# Sensing_ADC_Buffering.net
KiCad netlist of a schematic drawn in Altium Designer
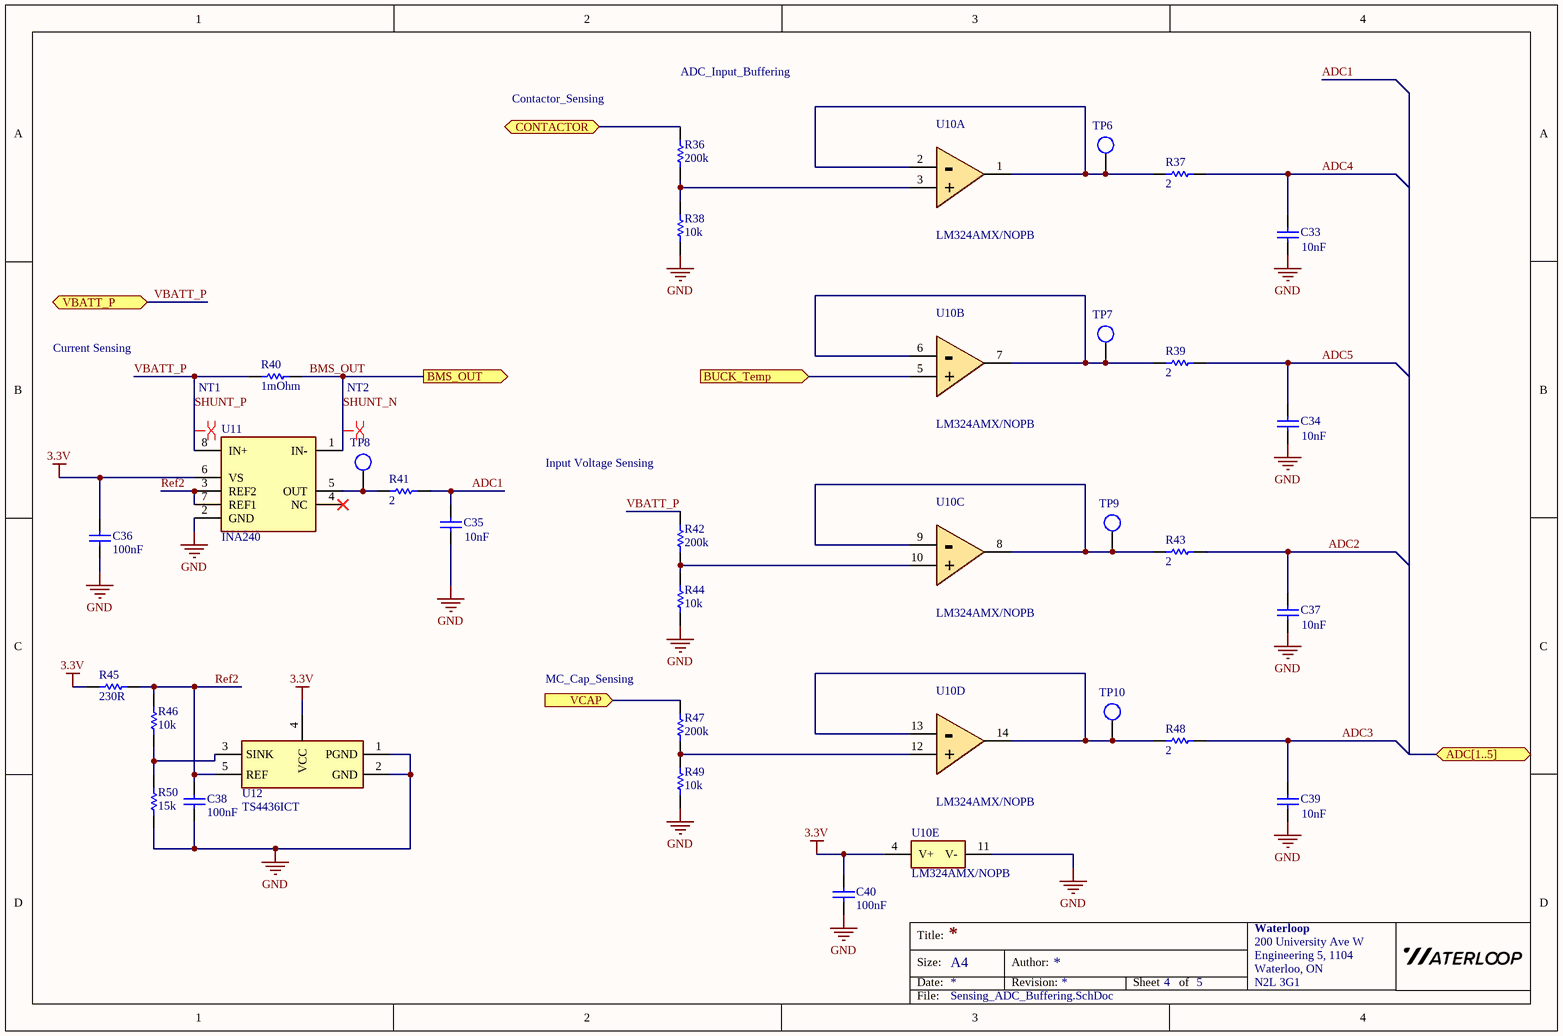
[diagram p0: Sensing_ADC_Buffering.SchDoc]

(export (version "E")
  (design (tool "Eeschema 10.0.6"))
  (components
    (comp (ref "C33")
      (value "10nF")
      (footprint "0805 - Capacitor")
      (description "CC0805JRX7R9BB103, CAP CER 10000PF 50V X7R 0805")
      (fields
        (field (name "MANUFACTURER") "YAGEO")
        (field (name "MANUFACTURER PART NUMBER") "CC0805MRX7R9BB103")
      )
      (libsource (lib "General") (part "Capacitor - Nonpolarized"))
    )
    (comp (ref "C34")
      (value "10nF")
      (footprint "0805 - Capacitor")
      (description "CC0805JRX7R9BB103, CAP CER 10000PF 50V X7R 0805")
      (fields
        (field (name "MANUFACTURER") "YAGEO")
        (field (name "MANUFACTURER PART NUMBER") "CC0805MRX7R9BB103")
      )
      (libsource (lib "General") (part "Capacitor - Nonpolarized"))
    )
    (comp (ref "C35")
      (value "10nF")
      (footprint "0805 - Capacitor")
      (description "CC0805JRX7R9BB103, CAP CER 10000PF 50V X7R 0805")
      (fields
        (field (name "MANUFACTURER") "YAGEO")
        (field (name "MANUFACTURER PART NUMBER") "CC0805MRX7R9BB103")
      )
      (libsource (lib "General") (part "Capacitor - Nonpolarized"))
    )
    (comp (ref "C36")
      (value "100nF")
      (footprint "0805 - Capacitor")
      (description "CC0805KRX7R9BB104, 0.1 µF  \r\n±10% 50V Ceramic Capacitor X7R 0805 (2012 Metric)")
      (fields
        (field (name "MANUFACTURER") "YAGEO")
        (field (name "MANUFACTURER PART NUMBER") "CC0805KRX7R9BB104")
      )
      (libsource (lib "General") (part "Capacitor - Nonpolarized"))
    )
    (comp (ref "C37")
      (value "10nF")
      (footprint "0805 - Capacitor")
      (description "CC0805JRX7R9BB103, CAP CER 10000PF 50V X7R 0805")
      (fields
        (field (name "MANUFACTURER") "YAGEO")
        (field (name "MANUFACTURER PART NUMBER") "CC0805MRX7R9BB103")
      )
      (libsource (lib "General") (part "Capacitor - Nonpolarized"))
    )
    (comp (ref "C38")
      (value "100nF")
      (footprint "0805 - Capacitor")
      (description "CC0805KRX7R9BB104, 0.1 µF  \r\n±10% 50V Ceramic Capacitor X7R 0805 (2012 Metric)")
      (fields
        (field (name "MANUFACTURER") "YAGEO")
        (field (name "MANUFACTURER PART NUMBER") "CC0805KRX7R9BB104")
      )
      (libsource (lib "General") (part "Capacitor - Nonpolarized"))
    )
    (comp (ref "C39")
      (value "10nF")
      (footprint "0805 - Capacitor")
      (description "CC0805JRX7R9BB103, CAP CER 10000PF 50V X7R 0805")
      (fields
        (field (name "MANUFACTURER") "YAGEO")
        (field (name "MANUFACTURER PART NUMBER") "CC0805MRX7R9BB103")
      )
      (libsource (lib "General") (part "Capacitor - Nonpolarized"))
    )
    (comp (ref "C40")
      (value "100nF")
      (footprint "0805 - Capacitor")
      (description "CC0805KRX7R9BB104, 0.1 µF  \r\n±10% 50V Ceramic Capacitor X7R 0805 (2012 Metric)")
      (fields
        (field (name "MANUFACTURER") "YAGEO")
        (field (name "MANUFACTURER PART NUMBER") "CC0805KRX7R9BB104")
      )
      (libsource (lib "General") (part "Capacitor - Nonpolarized"))
    )
    (comp (ref "NT1") (value "NetTie") (footprint "Net Tie") (libsource (lib "General") (part "Net Tie")))
    (comp (ref "NT2") (value "NetTie") (footprint "Net Tie") (libsource (lib "General") (part "Net Tie")))
    (comp (ref "R36")
      (value "200k")
      (footprint "0603 - Resistor")
      (description "RC0603FR-07200KL. 200 kOhms ±1% 0.1W, 1/10W Chip Resistor 0603 (1608 Metric) Thick Film")
      (fields
        (field (name "MANUFACTURER PART NUMBER") "RC0603FR-07200KL")
        (field (name "MANUFACTURER") "YAGEO")
      )
      (libsource (lib "General") (part "Resistor"))
    )
    (comp (ref "R37")
      (value "2")
      (footprint "0603 - Resistor")
      (description "RC0603FR-072RL, RES 2 OHM 1% 1/10W 0603")
      (fields
        (field (name "MANUFACTURER PART NUMBER") "RC0603FR-072RL")
        (field (name "MANUFACTURER") "YAGEO")
      )
      (libsource (lib "General") (part "Resistor"))
    )
    (comp (ref "R38")
      (value "10k")
      (footprint "0603 - Resistor")
      (fields
        (field (name "MANUFACTURER PART NUMBER") "RC0603FR-0710KL")
        (field (name "MANUFACTURER") "Yageo")
        (field (name "Comment") "Res2")
      )
      (libsource (lib "General") (part "Resistor"))
    )
    (comp (ref "R39")
      (value "2")
      (footprint "0603 - Resistor")
      (description "RC0603FR-072RL, RES 2 OHM 1% 1/10W 0603")
      (fields
        (field (name "MANUFACTURER PART NUMBER") "RC0603FR-072RL")
        (field (name "MANUFACTURER") "YAGEO")
      )
      (libsource (lib "General") (part "Resistor"))
    )
    (comp (ref "R40")
      (value "1mOhm")
      (footprint "2512 - RESISTOR")
      (description "SCMM2512S5-R001F, RES 0.001 OHM 1% 5W 2512")
      (fields
        (field (name "MANUFACTURER PART NUMBER") "VSML2512S5-R001F")
        (field (name "MANUFACTURER") "Delta Electronics/Cyntec")
      )
      (libsource (lib "General") (part "Resistor"))
    )
    (comp (ref "R41")
      (value "2")
      (footprint "0603 - Resistor")
      (description "RC0603FR-072RL, RES 2 OHM 1% 1/10W 0603")
      (fields
        (field (name "MANUFACTURER PART NUMBER") "RC0603FR-072RL")
        (field (name "MANUFACTURER") "YAGEO")
      )
      (libsource (lib "General") (part "Resistor"))
    )
    (comp (ref "R42")
      (value "200k")
      (footprint "0603 - Resistor")
      (description "RC0603FR-07200KL. 200 kOhms ±1% 0.1W, 1/10W Chip Resistor 0603 (1608 Metric) Thick Film")
      (fields
        (field (name "MANUFACTURER PART NUMBER") "RC0603FR-07200KL")
        (field (name "MANUFACTURER") "YAGEO")
      )
      (libsource (lib "General") (part "Resistor"))
    )
    (comp (ref "R43")
      (value "2")
      (footprint "0603 - Resistor")
      (description "RC0603FR-072RL, RES 2 OHM 1% 1/10W 0603")
      (fields
        (field (name "MANUFACTURER PART NUMBER") "RC0603FR-072RL")
        (field (name "MANUFACTURER") "YAGEO")
      )
      (libsource (lib "General") (part "Resistor"))
    )
    (comp (ref "R44")
      (value "10k")
      (footprint "0603 - Resistor")
      (fields
        (field (name "MANUFACTURER PART NUMBER") "RC0603FR-0710KL")
        (field (name "MANUFACTURER") "Yageo")
        (field (name "Comment") "Res2")
      )
      (libsource (lib "General") (part "Resistor"))
    )
    (comp (ref "R45")
      (value "230R")
      (footprint "0603 - Resistor")
      (fields
        (field (name "MANUFACTURER PART NUMBER") "RC0603FR-07232RL")
        (field (name "MANUFACTURER") "YAGEO")
        (field (name "Comment") "Res2")
      )
      (libsource (lib "General") (part "Resistor"))
    )
    (comp (ref "R46")
      (value "10k")
      (footprint "0603 - Resistor")
      (fields
        (field (name "MANUFACTURER PART NUMBER") "RC0603FR-0710KL")
        (field (name "MANUFACTURER") "Yageo")
        (field (name "Comment") "Res2")
      )
      (libsource (lib "General") (part "Resistor"))
    )
    (comp (ref "R47")
      (value "200k")
      (footprint "0603 - Resistor")
      (description "RC0603FR-07200KL. 200 kOhms ±1% 0.1W, 1/10W Chip Resistor 0603 (1608 Metric) Thick Film")
      (fields
        (field (name "MANUFACTURER PART NUMBER") "RC0603FR-07200KL")
        (field (name "MANUFACTURER") "YAGEO")
      )
      (libsource (lib "General") (part "Resistor"))
    )
    (comp (ref "R48")
      (value "2")
      (footprint "0603 - Resistor")
      (description "RC0603FR-072RL, RES 2 OHM 1% 1/10W 0603")
      (fields
        (field (name "MANUFACTURER PART NUMBER") "RC0603FR-072RL")
        (field (name "MANUFACTURER") "YAGEO")
      )
      (libsource (lib "General") (part "Resistor"))
    )
    (comp (ref "R49")
      (value "10k")
      (footprint "0603 - Resistor")
      (fields
        (field (name "MANUFACTURER PART NUMBER") "ERJ-3GEYJ103V")
        (field (name "MANUFACTURER") "Panasonic Electronic Components")
      )
      (libsource (lib "General") (part "Resistor"))
    )
    (comp (ref "R50")
      (value "15k")
      (footprint "0603 - Resistor")
      (fields
        (field (name "MANUFACTURER PART NUMBER") "RC0603FR-0715KL")
        (field (name "MANUFACTURER") "YAGEO")
        (field (name "Comment") "Res2")
      )
      (libsource (lib "General") (part "Resistor"))
    )
    (comp (ref "TP6")
      (value "~")
      (footprint "Test Point - 5002")
      (description "Test Point")
      (libsource (lib "General") (part "Test Point"))
    )
    (comp (ref "TP7")
      (value "~")
      (footprint "Test Point - 5002")
      (description "Test Point")
      (libsource (lib "General") (part "Test Point"))
    )
    (comp (ref "TP8")
      (value "~")
      (footprint "Test Point - 5002")
      (description "Test Point")
      (libsource (lib "General") (part "Test Point"))
    )
    (comp (ref "TP9")
      (value "~")
      (footprint "Test Point - 5002")
      (description "Test Point")
      (libsource (lib "General") (part "Test Point"))
    )
    (comp (ref "TP10")
      (value "~")
      (footprint "Test Point - 5002")
      (description "Test Point")
      (libsource (lib "General") (part "Test Point"))
    )
    (comp (ref "U10")
      (value "LM324AMX/NOPB")
      (footprint "LM324AMX/NOPB")
      (description "LM324AMX/NOPB, Gen Purp 4Ch Opamp")
      (fields (field (name "MANUFACTURER") "TI"))
      (libsource (lib "GeneralComponents") (part "LM324AMX/NOPB"))
    )
    (comp (ref "U11")
      (value "INA240")
      (footprint "INA240")
      (description "INA240A2, -4V to 80V Current Sense Amplifier")
      (fields
        (field (name "MANUFACTURER") "Texas Instruments")
        (field (name "MANUFACTURER PART NUMBER") "INA240A2DR")
      )
      (libsource (lib "GeneralComponents") (part "INA240"))
    )
    (comp (ref "U12")
      (value "TS4436ICT")
      (footprint "SOT323")
      (description "Shunt Voltage Reference IC Adjustable 0.6V 1.8 VV ±1% 20 mA SC-70-5")
      (fields (field (name "MANUFACTURER") "ST"))
      (libsource (lib "GeneralComponents") (part "TS4436ICT"))
    )
  )
  (nets
    (net (code "1") (name "/ADC1") (class "Default")
      (node (ref "C35") (pin "2") (pinfunction "2_2") (pintype "passive"))
      (node (ref "R41") (pin "2") (pinfunction "2_2") (pintype "passive"))
    )
    (net (code "2") (name "/ADC2") (class "Default")
      (node (ref "C37") (pin "2") (pinfunction "2_2") (pintype "passive"))
      (node (ref "R43") (pin "2") (pinfunction "2_2") (pintype "passive"))
    )
    (net (code "3") (name "/ADC3") (class "Default")
      (node (ref "C39") (pin "2") (pinfunction "2_2") (pintype "passive"))
      (node (ref "R48") (pin "2") (pinfunction "2_2") (pintype "passive"))
    )
    (net (code "4") (name "/ADC4") (class "Default")
      (node (ref "C33") (pin "2") (pinfunction "2_2") (pintype "passive"))
      (node (ref "R37") (pin "2") (pinfunction "2_2") (pintype "passive"))
    )
    (net (code "5") (name "/ADC5") (class "Default")
      (node (ref "C34") (pin "2") (pinfunction "2_2") (pintype "passive"))
      (node (ref "R39") (pin "2") (pinfunction "2_2") (pintype "passive"))
    )
    (net (code "7") (name "/BMS_OUT") (class "Default")
      (node (ref "NT2") (pin "2") (pinfunction "2_2") (pintype "passive"))
      (node (ref "R40") (pin "2") (pinfunction "2_2") (pintype "passive"))
    )
    (net (code "8") (name "/BUCK_Temp") (class "Default")
      (node (ref "U10") (pin "5") (pinfunction "+_5") (pintype "passive"))
    )
    (net (code "9") (name "/CONTACTOR") (class "Default")
      (node (ref "R36") (pin "2") (pinfunction "2_2") (pintype "passive"))
    )
    (net (code "10") (name "/Ref2") (class "Default")
      (node (ref "C38") (pin "2") (pinfunction "2_2") (pintype "passive"))
      (node (ref "R45") (pin "1") (pinfunction "1_1") (pintype "passive"))
      (node (ref "R46") (pin "1") (pinfunction "1_1") (pintype "passive"))
      (node (ref "U11") (pin "3") (pinfunction "REF2_3") (pintype "passive"))
      (node (ref "U11") (pin "7") (pinfunction "REF1_7") (pintype "passive"))
      (node (ref "U12") (pin "5") (pinfunction "REF_5") (pintype "passive"))
    )
    (net (code "11") (name "/SHUNT_N") (class "Default")
      (node (ref "NT2") (pin "1") (pinfunction "1_1") (pintype "passive"))
      (node (ref "U11") (pin "1") (pinfunction "IN-_1") (pintype "passive"))
    )
    (net (code "12") (name "/SHUNT_P") (class "Default")
      (node (ref "NT1") (pin "1") (pinfunction "1_1") (pintype "passive"))
      (node (ref "U11") (pin "8") (pinfunction "IN+_8") (pintype "passive"))
    )
    (net (code "13") (name "/VBATT_P") (class "Default")
      (node (ref "NT1") (pin "2") (pinfunction "2_2") (pintype "passive"))
      (node (ref "R40") (pin "1") (pinfunction "1_1") (pintype "passive"))
      (node (ref "R42") (pin "2") (pinfunction "2_2") (pintype "passive"))
    )
    (net (code "14") (name "/VCAP") (class "Default")
      (node (ref "R47") (pin "2") (pinfunction "2_2") (pintype "passive"))
    )
    (net (code "15") (name "3.3V") (class "Default")
      (node (ref "C36") (pin "2") (pinfunction "2_2") (pintype "passive"))
      (node (ref "C40") (pin "2") (pinfunction "2_2") (pintype "passive"))
      (node (ref "R45") (pin "2") (pinfunction "2_2") (pintype "passive"))
      (node (ref "U10") (pin "4") (pinfunction "V+_4") (pintype "passive"))
      (node (ref "U11") (pin "6") (pinfunction "VS_6") (pintype "power_in"))
      (node (ref "U12") (pin "4") (pinfunction "VCC_4") (pintype "passive"))
    )
    (net (code "16") (name "GND") (class "Default")
      (node (ref "C33") (pin "1") (pinfunction "1_1") (pintype "passive"))
      (node (ref "C34") (pin "1") (pinfunction "1_1") (pintype "passive"))
      (node (ref "C35") (pin "1") (pinfunction "1_1") (pintype "passive"))
      (node (ref "C36") (pin "1") (pinfunction "1_1") (pintype "passive"))
      (node (ref "C37") (pin "1") (pinfunction "1_1") (pintype "passive"))
      (node (ref "C38") (pin "1") (pinfunction "1_1") (pintype "passive"))
      (node (ref "C39") (pin "1") (pinfunction "1_1") (pintype "passive"))
      (node (ref "C40") (pin "1") (pinfunction "1_1") (pintype "passive"))
      (node (ref "R38") (pin "1") (pinfunction "1_1") (pintype "passive"))
      (node (ref "R44") (pin "1") (pinfunction "1_1") (pintype "passive"))
      (node (ref "R49") (pin "1") (pinfunction "1_1") (pintype "passive"))
      (node (ref "R50") (pin "2") (pinfunction "2_2") (pintype "passive"))
      (node (ref "U10") (pin "11") (pinfunction "V-_11") (pintype "passive"))
      (node (ref "U11") (pin "2") (pinfunction "GND_2") (pintype "power_in"))
      (node (ref "U12") (pin "1") (pinfunction "PGND_1") (pintype "passive"))
      (node (ref "U12") (pin "2") (pinfunction "GND_2") (pintype "passive"))
    )
    (net (code "17") (name "Net-(TP6-0)") (class "Default")
      (node (ref "R37") (pin "1") (pinfunction "1_1") (pintype "passive"))
      (node (ref "TP6") (pin "1") (pinfunction "0_1") (pintype "passive"))
      (node (ref "U10") (pin "1") (pinfunction "14_1") (pintype "passive"))
      (node (ref "U10") (pin "2") (pinfunction "-_2") (pintype "passive"))
    )
    (net (code "18") (name "Net-(TP7-0)") (class "Default")
      (node (ref "R39") (pin "1") (pinfunction "1_1") (pintype "passive"))
      (node (ref "TP7") (pin "1") (pinfunction "0_1") (pintype "passive"))
      (node (ref "U10") (pin "6") (pinfunction "-_6") (pintype "passive"))
      (node (ref "U10") (pin "7") (pinfunction "14_7") (pintype "passive"))
    )
    (net (code "19") (name "Net-(TP8-0)") (class "Default")
      (node (ref "R41") (pin "1") (pinfunction "1_1") (pintype "passive"))
      (node (ref "TP8") (pin "1") (pinfunction "0_1") (pintype "passive"))
      (node (ref "U11") (pin "5") (pinfunction "OUT_5") (pintype "passive"))
    )
    (net (code "20") (name "Net-(TP9-0)") (class "Default")
      (node (ref "R43") (pin "1") (pinfunction "1_1") (pintype "passive"))
      (node (ref "TP9") (pin "1") (pinfunction "0_1") (pintype "passive"))
      (node (ref "U10") (pin "8") (pinfunction "14_8") (pintype "passive"))
      (node (ref "U10") (pin "9") (pinfunction "-_9") (pintype "passive"))
    )
    (net (code "21") (name "Net-(TP10-0)") (class "Default")
      (node (ref "R48") (pin "1") (pinfunction "1_1") (pintype "passive"))
      (node (ref "TP10") (pin "1") (pinfunction "0_1") (pintype "passive"))
      (node (ref "U10") (pin "13") (pinfunction "-_13") (pintype "passive"))
      (node (ref "U10") (pin "14") (pinfunction "14_14") (pintype "passive"))
    )
    (net (code "22") (name "Net-(U10A-+)") (class "Default")
      (node (ref "R36") (pin "1") (pinfunction "1_1") (pintype "passive"))
      (node (ref "R38") (pin "2") (pinfunction "2_2") (pintype "passive"))
      (node (ref "U10") (pin "3") (pinfunction "+_3") (pintype "passive"))
    )
    (net (code "23") (name "Net-(U10C-+)") (class "Default")
      (node (ref "R42") (pin "1") (pinfunction "1_1") (pintype "passive"))
      (node (ref "R44") (pin "2") (pinfunction "2_2") (pintype "passive"))
      (node (ref "U10") (pin "10") (pinfunction "+_10") (pintype "passive"))
    )
    (net (code "24") (name "Net-(U10D-+)") (class "Default")
      (node (ref "R47") (pin "1") (pinfunction "1_1") (pintype "passive"))
      (node (ref "R49") (pin "2") (pinfunction "2_2") (pintype "passive"))
      (node (ref "U10") (pin "12") (pinfunction "+_12") (pintype "passive"))
    )
    (net (code "25") (name "Net-(U12-SINK)") (class "Default")
      (node (ref "R46") (pin "2") (pinfunction "2_2") (pintype "passive"))
      (node (ref "R50") (pin "1") (pinfunction "1_1") (pintype "passive"))
      (node (ref "U12") (pin "3") (pinfunction "SINK_3") (pintype "passive"))
    )
    (net (code "26") (name "unconnected-(U11-NC-Pad4)") (class "Default")
      (node (ref "U11") (pin "4") (pinfunction "NC_4") (pintype "passive+no_connect"))
    )
  )
)
